# power.net
KiCad netlist of a schematic drawn in Altium Designer
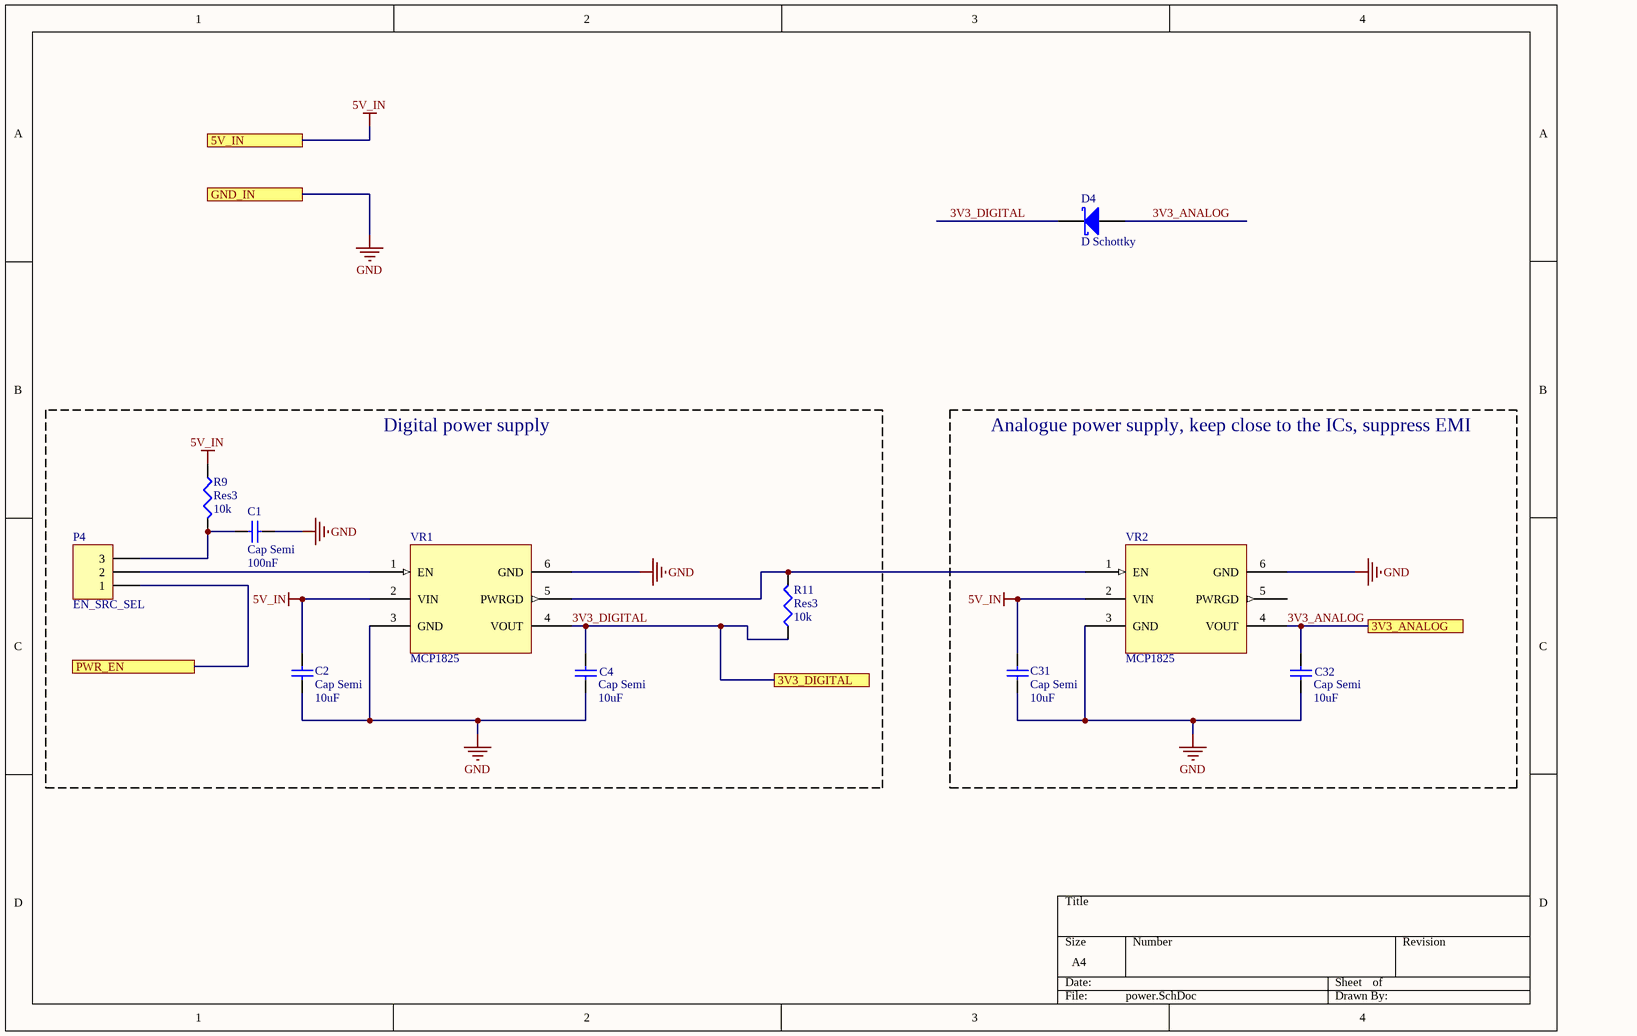
[diagram p0: power.SchDoc]

(export (version "E")
  (design (tool "Eeschema 10.0.6"))
  (components
    (comp (ref "C1")
      (value "Cap Semi")
      (footprint "C1206")
      (description "Capacitor (Semiconductor SIM Model)")
      (fields (field (name "ALTIUM_VALUE") "100nF") (field (name "PUBLISHER") "Altium Limited"))
      (libsource (lib "Miscellaneous Devices") (part "Cap Semi"))
    )
    (comp (ref "C2")
      (value "Cap Semi")
      (footprint "C1210")
      (description "Capacitor (Semiconductor SIM Model)")
      (fields (field (name "ALTIUM_VALUE") "10uF") (field (name "PUBLISHER") "Altium Limited"))
      (libsource (lib "Miscellaneous Devices") (part "Cap Semi"))
    )
    (comp (ref "C4")
      (value "Cap Semi")
      (footprint "C1210")
      (description "Capacitor (Semiconductor SIM Model)")
      (fields (field (name "ALTIUM_VALUE") "10uF") (field (name "PUBLISHER") "Altium Limited"))
      (libsource (lib "Miscellaneous Devices") (part "Cap Semi"))
    )
    (comp (ref "C31")
      (value "Cap Semi")
      (footprint "C1210")
      (description "Capacitor (Semiconductor SIM Model)")
      (fields (field (name "ALTIUM_VALUE") "10uF") (field (name "PUBLISHER") "Altium Limited"))
      (libsource (lib "Miscellaneous Devices") (part "Cap Semi"))
    )
    (comp (ref "C32")
      (value "Cap Semi")
      (footprint "C1210")
      (description "Capacitor (Semiconductor SIM Model)")
      (fields (field (name "ALTIUM_VALUE") "10uF") (field (name "PUBLISHER") "Altium Limited"))
      (libsource (lib "Miscellaneous Devices") (part "Cap Semi"))
    )
    (comp (ref "D4")
      (value "D Schottky")
      (footprint "SMB")
      (description "Schottky Diode")
      (fields (field (name "PUBLISHER") "Altium Limited"))
      (libsource (lib "Miscellaneous Devices") (part "D Schottky"))
    )
    (comp (ref "P4")
      (value "EN_SRC_SEL")
      (footprint "HDR1X3")
      (description "Header, 3-Pin")
      (fields (field (name "PUBLISHER") "Altium Limited"))
      (libsource (lib "Miscellaneous Connectors") (part "Header 3"))
    )
    (comp (ref "R9")
      (value "Res3")
      (footprint "J1-0603")
      (description "Resistor")
      (fields (field (name "ALTIUM_VALUE") "10k") (field (name "PUBLISHER") "Altium Limited"))
      (libsource (lib "Miscellaneous Devices") (part "Res3"))
    )
    (comp (ref "R11")
      (value "Res3")
      (footprint "J1-0603")
      (description "Resistor")
      (fields (field (name "ALTIUM_VALUE") "10k") (field (name "PUBLISHER") "Altium Limited"))
      (libsource (lib "Miscellaneous Devices") (part "Res3"))
    )
    (comp (ref "VR1")
      (value "MCP1825")
      (footprint "SOT-223-6")
      (description "3.3V Voltage regulator")
      (libsource (lib "RPi_sensor_expansion_board_library") (part "MCP1825"))
    )
    (comp (ref "VR2")
      (value "MCP1825")
      (footprint "SOT-223-6")
      (description "3.3V Voltage regulator")
      (libsource (lib "RPi_sensor_expansion_board_library") (part "MCP1825"))
    )
  )
  (nets
    (net (code "1") (name "/3V3_ANALOG") (class "Default")
      (node (ref "C32") (pin "2") (pinfunction "2_2") (pintype "passive"))
      (node (ref "D4") (pin "1") (pinfunction "A_1") (pintype "passive"))
      (node (ref "VR2") (pin "4") (pinfunction "VOUT_4") (pintype "power_in"))
    )
    (net (code "2") (name "/3V3_DIGITAL") (class "Default")
      (node (ref "C4") (pin "2") (pinfunction "2_2") (pintype "passive"))
      (node (ref "D4") (pin "2") (pinfunction "K_2") (pintype "passive"))
      (node (ref "R11") (pin "1") (pinfunction "1_1") (pintype "passive"))
      (node (ref "VR1") (pin "4") (pinfunction "VOUT_4") (pintype "power_in"))
    )
    (net (code "3") (name "/PWR_EN") (class "Default")
      (node (ref "P4") (pin "1") (pinfunction "1_1") (pintype "passive"))
    )
    (net (code "4") (name "5V_IN") (class "Default")
      (node (ref "C2") (pin "2") (pinfunction "2_2") (pintype "passive"))
      (node (ref "C31") (pin "2") (pinfunction "2_2") (pintype "passive"))
      (node (ref "R9") (pin "1") (pinfunction "1_1") (pintype "passive"))
      (node (ref "VR1") (pin "2") (pinfunction "VIN_2") (pintype "power_in"))
      (node (ref "VR2") (pin "2") (pinfunction "VIN_2") (pintype "power_in"))
    )
    (net (code "5") (name "GND") (class "Default")
      (node (ref "C1") (pin "1") (pinfunction "1_1") (pintype "passive"))
      (node (ref "C2") (pin "1") (pinfunction "1_1") (pintype "passive"))
      (node (ref "C31") (pin "1") (pinfunction "1_1") (pintype "passive"))
      (node (ref "C32") (pin "1") (pinfunction "1_1") (pintype "passive"))
      (node (ref "C4") (pin "1") (pinfunction "1_1") (pintype "passive"))
      (node (ref "VR1") (pin "3") (pinfunction "GND_3") (pintype "power_in"))
      (node (ref "VR1") (pin "6") (pinfunction "GND_6") (pintype "power_in"))
      (node (ref "VR2") (pin "3") (pinfunction "GND_3") (pintype "power_in"))
      (node (ref "VR2") (pin "6") (pinfunction "GND_6") (pintype "power_in"))
    )
    (net (code "6") (name "Net-(C1-Pad2)") (class "Default")
      (node (ref "C1") (pin "2") (pinfunction "2_2") (pintype "passive"))
      (node (ref "P4") (pin "3") (pinfunction "3_3") (pintype "passive"))
      (node (ref "R9") (pin "2") (pinfunction "2_2") (pintype "passive"))
    )
    (net (code "7") (name "Net-(VR1-EN)") (class "Default")
      (node (ref "P4") (pin "2") (pinfunction "2_2") (pintype "passive"))
      (node (ref "VR1") (pin "1") (pinfunction "EN_1") (pintype "input"))
    )
    (net (code "8") (name "Net-(VR1-PWRGD)") (class "Default")
      (node (ref "R11") (pin "2") (pinfunction "2_2") (pintype "passive"))
      (node (ref "VR1") (pin "5") (pinfunction "PWRGD_5") (pintype "output"))
      (node (ref "VR2") (pin "1") (pinfunction "EN_1") (pintype "input"))
    )
    (net (code "9") (name "unconnected-(VR2-PWRGD-Pad5)") (class "Default")
      (node (ref "VR2") (pin "5") (pinfunction "PWRGD_5") (pintype "output"))
    )
  )
)
